# Sensors_Sch.net
KiCad netlist of a schematic drawn in Altium Designer
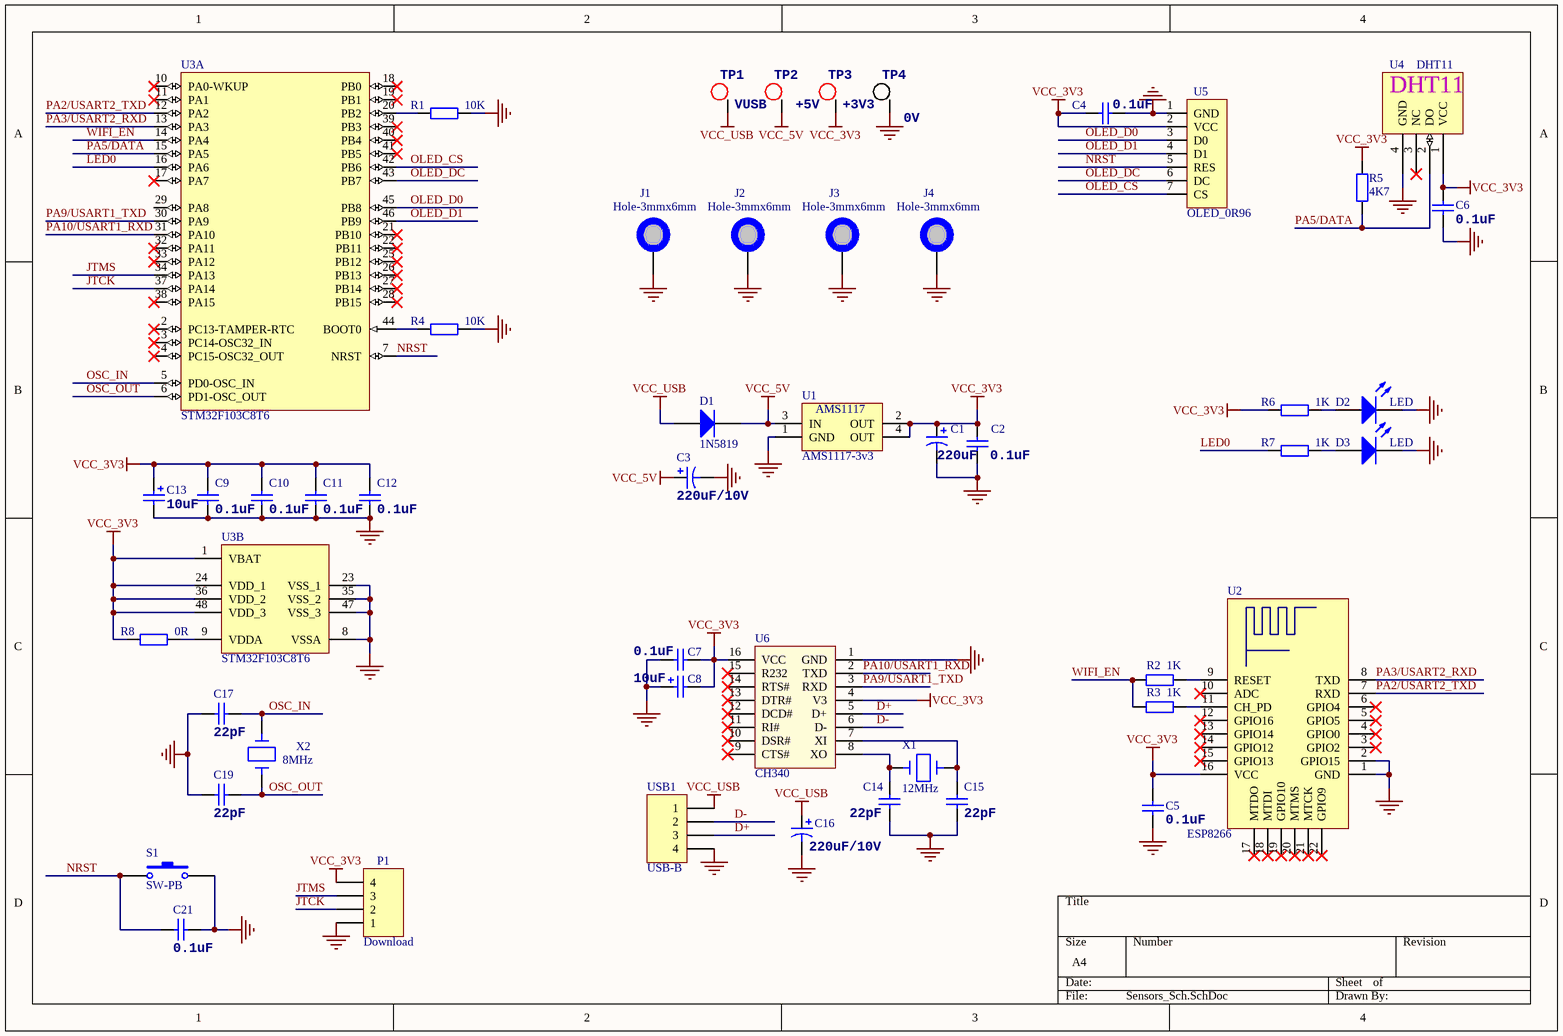
[diagram p0: Sensors_Sch.SchDoc]

(export (version "E")
  (design (tool "Eeschema 10.0.6"))
  (components
    (comp (ref "C1")
      (value "220uF")
      (footprint "C_SMD(6.3x5.3)")
      (description "CAP ALUM POLY 150UF 20% 10V SMD")
      (fields
        (field (name "MANUFACTURER") "KEMET")
        (field (name "MANUFACTURER PART NUMBER") "A765EB157M1ALAE022")
      )
      (libsource (lib "Desiger_Schlib") (part "Cap3"))
    )
    (comp (ref "C2")
      (value "0.1uF")
      (footprint "C0603")
      (description "CAP CER 10000PF 100V X7R 0603")
      (fields
        (field (name "MANUFACTURER") "TDK Corporation")
        (field (name "MANUFACTURER PART NUMBER") "C1608X7R2A103K080AA")
      )
      (libsource (lib "Desiger_Schlib") (part "Cap1"))
    )
    (comp (ref "C3")
      (value "220uF/10V")
      (footprint "C_SMD(6.3x5.3)")
      (description "CAP ALUM POLY 150UF 20% 10V SMD")
      (fields
        (field (name "MANUFACTURER") "KEMET")
        (field (name "MANUFACTURER PART NUMBER") "A765EB157M1ALAE022")
      )
      (libsource (lib "Desiger_Schlib") (part "Cap3"))
    )
    (comp (ref "C4")
      (value "0.1uF")
      (footprint "C0603")
      (description "CAP CER 10000PF 100V X7R 0603")
      (fields
        (field (name "MANUFACTURER") "TDK Corporation")
        (field (name "MANUFACTURER PART NUMBER") "C1608X7R2A103K080AA")
      )
      (libsource (lib "Desiger_Schlib") (part "Cap1"))
    )
    (comp (ref "C5")
      (value "0.1uF")
      (footprint "C0603")
      (description "CAP CER 10000PF 100V X7R 0603")
      (fields
        (field (name "MANUFACTURER") "TDK Corporation")
        (field (name "MANUFACTURER PART NUMBER") "C1608X7R2A103K080AA")
      )
      (libsource (lib "Desiger_Schlib") (part "Cap1"))
    )
    (comp (ref "C6")
      (value "0.1uF")
      (footprint "C0603")
      (description "CAP CER 10000PF 100V X7R 0603")
      (fields
        (field (name "MANUFACTURER") "TDK Corporation")
        (field (name "MANUFACTURER PART NUMBER") "C1608X7R2A103K080AA")
      )
      (libsource (lib "Desiger_Schlib") (part "Cap1"))
    )
    (comp (ref "C7")
      (value "0.1uF")
      (footprint "C0603")
      (description "CAP CER 10000PF 100V X7R 0603")
      (fields
        (field (name "MANUFACTURER") "TDK Corporation")
        (field (name "MANUFACTURER PART NUMBER") "C1608X7R2A103K080AA")
      )
      (libsource (lib "Desiger_Schlib") (part "Cap1"))
    )
    (comp (ref "C8")
      (value "10uF")
      (footprint "TAC1206")
      (description "CAP TANT 10UF 10V 10% 1206")
      (fields
        (field (name "MANUFACTURER") "KEMET")
        (field (name "MANUFACTURER PART NUMBER") "T491A106K010AT7280")
      )
      (libsource (lib "Desiger_Schlib") (part "Cap2"))
    )
    (comp (ref "C9")
      (value "0.1uF")
      (footprint "C0603")
      (description "CAP CER 10000PF 100V X7R 0603")
      (fields
        (field (name "MANUFACTURER") "TDK Corporation")
        (field (name "MANUFACTURER PART NUMBER") "C1608X7R2A103K080AA")
      )
      (libsource (lib "Desiger_Schlib") (part "Cap1"))
    )
    (comp (ref "C10")
      (value "0.1uF")
      (footprint "C0603")
      (description "CAP CER 10000PF 100V X7R 0603")
      (fields
        (field (name "MANUFACTURER") "TDK Corporation")
        (field (name "MANUFACTURER PART NUMBER") "C1608X7R2A103K080AA")
      )
      (libsource (lib "Desiger_Schlib") (part "Cap1"))
    )
    (comp (ref "C11")
      (value "0.1uF")
      (footprint "C0603")
      (description "CAP CER 10000PF 100V X7R 0603")
      (fields
        (field (name "MANUFACTURER") "TDK Corporation")
        (field (name "MANUFACTURER PART NUMBER") "C1608X7R2A103K080AA")
      )
      (libsource (lib "Desiger_Schlib") (part "Cap1"))
    )
    (comp (ref "C12")
      (value "0.1uF")
      (footprint "C0603")
      (description "CAP CER 10000PF 100V X7R 0603")
      (fields
        (field (name "MANUFACTURER") "TDK Corporation")
        (field (name "MANUFACTURER PART NUMBER") "C1608X7R2A103K080AA")
      )
      (libsource (lib "Desiger_Schlib") (part "Cap1"))
    )
    (comp (ref "C13")
      (value "10uF")
      (footprint "TAC1206")
      (description "CAP TANT 10UF 10V 10% 1206")
      (fields
        (field (name "MANUFACTURER") "KEMET")
        (field (name "MANUFACTURER PART NUMBER") "T491A106K010AT7280")
      )
      (libsource (lib "Desiger_Schlib") (part "Cap2"))
    )
    (comp (ref "C14")
      (value "22pF")
      (footprint "C0603")
      (description "CAP CER 10000PF 100V X7R 0603")
      (fields
        (field (name "MANUFACTURER") "TDK Corporation")
        (field (name "MANUFACTURER PART NUMBER") "C1608X7R2A103K080AA")
      )
      (libsource (lib "Desiger_Schlib") (part "Cap1"))
    )
    (comp (ref "C15")
      (value "22pF")
      (footprint "C0603")
      (description "CAP CER 10000PF 100V X7R 0603")
      (fields
        (field (name "MANUFACTURER") "TDK Corporation")
        (field (name "MANUFACTURER PART NUMBER") "C1608X7R2A103K080AA")
      )
      (libsource (lib "Desiger_Schlib") (part "Cap1"))
    )
    (comp (ref "C16")
      (value "220uF/10V")
      (footprint "C_SMD(6.3x5.3)")
      (description "CAP ALUM POLY 150UF 20% 10V SMD")
      (fields
        (field (name "MANUFACTURER") "KEMET")
        (field (name "MANUFACTURER PART NUMBER") "A765EB157M1ALAE022")
      )
      (libsource (lib "Desiger_Schlib") (part "Cap3"))
    )
    (comp (ref "C17")
      (value "22pF")
      (footprint "C0603")
      (description "CAP CER 10000PF 100V X7R 0603")
      (fields
        (field (name "MANUFACTURER") "TDK Corporation")
        (field (name "MANUFACTURER PART NUMBER") "C1608X7R2A103K080AA")
      )
      (libsource (lib "Desiger_Schlib") (part "Cap1"))
    )
    (comp (ref "C19")
      (value "22pF")
      (footprint "C0603")
      (description "CAP CER 10000PF 100V X7R 0603")
      (fields
        (field (name "MANUFACTURER") "TDK Corporation")
        (field (name "MANUFACTURER PART NUMBER") "C1608X7R2A103K080AA")
      )
      (libsource (lib "Desiger_Schlib") (part "Cap1"))
    )
    (comp (ref "C21")
      (value "0.1uF")
      (footprint "C0603")
      (description "CAP CER 10000PF 100V X7R 0603")
      (fields
        (field (name "MANUFACTURER") "TDK Corporation")
        (field (name "MANUFACTURER PART NUMBER") "C1608X7R2A103K080AA")
      )
      (libsource (lib "Desiger_Schlib") (part "Cap1"))
    )
    (comp (ref "D1")
      (value "1N5819")
      (footprint "Desiger_Pcblib:SOD123")
      (description "Default Diode")
      (fields (field (name "PUBLISHER") "Altium Limited"))
      (libsource (lib "Desiger_Schlib") (part "Diode"))
    )
    (comp (ref "D2")
      (value "LED")
      (footprint "LED_0603")
      (description "Typical RED GaAs LED")
      (fields (field (name "PUBLISHER") "Altium Limited"))
      (libsource (lib "Desiger_Schlib") (part "LED"))
    )
    (comp (ref "D3")
      (value "LED")
      (footprint "LED_0603")
      (description "Typical RED GaAs LED")
      (fields (field (name "PUBLISHER") "Altium Limited"))
      (libsource (lib "Desiger_Schlib") (part "LED"))
    )
    (comp (ref "J1")
      (value "Hole-3mmx6mm")
      (footprint "M3x7+6_L")
      (libsource (lib "Desiger_Schlib") (part "HOLED"))
    )
    (comp (ref "J2")
      (value "Hole-3mmx6mm")
      (footprint "M3x7+6_L")
      (libsource (lib "Desiger_Schlib") (part "HOLED"))
    )
    (comp (ref "J3")
      (value "Hole-3mmx6mm")
      (footprint "M3x7+6_L")
      (libsource (lib "Desiger_Schlib") (part "HOLED"))
    )
    (comp (ref "J4")
      (value "Hole-3mmx6mm")
      (footprint "M3x7+6_L")
      (libsource (lib "Desiger_Schlib") (part "HOLED"))
    )
    (comp (ref "P1")
      (value "Download")
      (footprint "HDR1X4")
      (description "Header, 4-Pin")
      (fields (field (name "PUBLISHER") "Altium Limited"))
      (libsource (lib "Miscellaneous Connectors") (part "Header 4"))
    )
    (comp (ref "R1")
      (value "10K")
      (footprint "R0603")
      (description "贴片电阻")
      (fields (field (name "版权归属") "源创客"))
      (libsource (lib "3.1   - 电阻-电容-电感") (part "R"))
    )
    (comp (ref "R2")
      (value "1K")
      (footprint "R0603")
      (description "贴片电阻")
      (fields (field (name "版权归属") "源创客"))
      (libsource (lib "3.1   - 电阻-电容-电感") (part "R"))
    )
    (comp (ref "R3")
      (value "1K")
      (footprint "R0603")
      (description "贴片电阻")
      (fields (field (name "版权归属") "源创客"))
      (libsource (lib "3.1   - 电阻-电容-电感") (part "R"))
    )
    (comp (ref "R4")
      (value "10K")
      (footprint "R0603")
      (description "贴片电阻")
      (fields (field (name "版权归属") "源创客"))
      (libsource (lib "3.1   - 电阻-电容-电感") (part "R"))
    )
    (comp (ref "R5")
      (value "4K7")
      (footprint "R0603")
      (description "贴片电阻")
      (fields (field (name "版权归属") "源创客"))
      (libsource (lib "3.1   - 电阻-电容-电感") (part "R"))
    )
    (comp (ref "R6")
      (value "1K")
      (footprint "R0603")
      (description "贴片电阻")
      (fields (field (name "版权归属") "源创客"))
      (libsource (lib "3.1   - 电阻-电容-电感") (part "R"))
    )
    (comp (ref "R7")
      (value "1K")
      (footprint "R0603")
      (description "贴片电阻")
      (fields (field (name "版权归属") "源创客"))
      (libsource (lib "3.1   - 电阻-电容-电感") (part "R"))
    )
    (comp (ref "R8")
      (value "0R")
      (footprint "R0603")
      (description "贴片电阻")
      (fields (field (name "版权归属") "源创客"))
      (libsource (lib "3.1   - 电阻-电容-电感") (part "R"))
    )
    (comp (ref "S1")
      (value "SW-PB")
      (footprint "micro button_2_SMD")
      (description "Switch")
      (fields (field (name "PUBLISHER") "Altium Limited"))
      (libsource (lib "Miscellaneous Devices") (part "SW-PB"))
    )
    (comp (ref "TP1")
      (value "VUSB")
      (footprint "TP")
      (description "正测试环")
      (libsource (lib "Desiger_Schlib") (part "TP+"))
    )
    (comp (ref "TP2")
      (value "+5V")
      (footprint "TP")
      (description "正测试环")
      (libsource (lib "Desiger_Schlib") (part "TP+"))
    )
    (comp (ref "TP3")
      (value "+3V3")
      (footprint "TP")
      (description "正测试环")
      (libsource (lib "Desiger_Schlib") (part "TP+"))
    )
    (comp (ref "TP4")
      (value "0V")
      (footprint "TP")
      (description "负测试环")
      (libsource (lib "Desiger_Schlib") (part "TP-"))
    )
    (comp (ref "U1")
      (value "AMS1117-3v3")
      (footprint "SOT223_L")
      (libsource (lib "Desiger_Schlib") (part "AMS1117-3v3"))
    )
    (comp (ref "U2")
      (value "ESP8266")
      (footprint "ESP8266")
      (libsource (lib "Desiger_Schlib") (part "ESP8266 Module"))
    )
    (comp (ref "U3")
      (value "STM32F103C8T6")
      (footprint "LQFP48 7X7_N")
      (libsource (lib "STMicroelectronics STM32 F1") (part "STM32F103C8T6"))
    )
    (comp (ref "U4")
      (value "DHT11")
      (footprint "DHT11")
      (description "GROVE TEMP/HUMIDITY SENSOR")
      (fields
        (field (name "MANUFACTURER") "Seeed Technology Co., Ltd")
        (field (name "MANUFACTURER PART NUMBER") "101020011")
      )
      (libsource (lib "Desiger_Schlib") (part "DHT11"))
    )
    (comp (ref "U5")
      (value "OLED_0R96")
      (footprint "OLED_0.96_SPI")
      (libsource (lib "Desiger_Schlib") (part "OLED_7P_0R96"))
    )
    (comp (ref "U6") (value "CH340") (footprint "SOIC_16") (libsource (lib "First Version") (part "CH340")))
    (comp (ref "USB1")
      (value "USB-B")
      (footprint "USB-B")
      (description "Header, 4-Pin")
      (fields (field (name "PUBLISHER") "Altium Limited"))
      (libsource (lib "") (part "Header 4_1"))
    )
    (comp (ref "X1")
      (value "12MHz")
      (footprint "HC-49SMD")
      (description "CRYSTAL 12.0000MHZ 18PF SMD")
      (fields
        (field (name "MANUFACTURER") "Abracon LLC")
        (field (name "MANUFACTURER PART NUMBER") "ABLS-12.000MHZ-B2-T")
      )
      (libsource (lib "Desiger_Schlib") (part "Crystal"))
    )
    (comp (ref "X2")
      (value "8MHz")
      (footprint "HC-49SMD")
      (description "CRYSTAL 12.0000MHZ 18PF SMD")
      (fields
        (field (name "MANUFACTURER") "Abracon LLC")
        (field (name "MANUFACTURER PART NUMBER") "ABLS-12.000MHZ-B2-T")
      )
      (libsource (lib "Desiger_Schlib") (part "Crystal"))
    )
  )
  (nets
    (net (code "1") (name "/D+") (class "Default")
      (node (ref "U6") (pin "5") (pinfunction "D+_5") (pintype "passive"))
      (node (ref "USB1") (pin "3") (pinfunction "3_3") (pintype "passive"))
    )
    (net (code "2") (name "/D-") (class "Default")
      (node (ref "U6") (pin "6") (pinfunction "D-_6") (pintype "passive"))
      (node (ref "USB1") (pin "2") (pinfunction "2_2") (pintype "passive"))
    )
    (net (code "3") (name "/JTCK") (class "Default")
      (node (ref "P1") (pin "2") (pinfunction "2_2") (pintype "passive"))
      (node (ref "U3") (pin "37") (pinfunction "PA14_37") (pintype "bidirectional"))
    )
    (net (code "4") (name "/JTMS") (class "Default")
      (node (ref "P1") (pin "3") (pinfunction "3_3") (pintype "passive"))
      (node (ref "U3") (pin "34") (pinfunction "PA13_34") (pintype "bidirectional"))
    )
    (net (code "5") (name "/LED0") (class "Default")
      (node (ref "R7") (pin "1") (pinfunction "1_1") (pintype "passive"))
      (node (ref "U3") (pin "16") (pinfunction "PA6_16") (pintype "bidirectional"))
    )
    (net (code "6") (name "/NRST") (class "Default")
      (node (ref "C21") (pin "2") (pinfunction "2_2") (pintype "passive"))
      (node (ref "S1") (pin "1") (pinfunction "1_1") (pintype "passive"))
      (node (ref "U3") (pin "7") (pinfunction "NRST_7") (pintype "bidirectional"))
      (node (ref "U5") (pin "5") (pinfunction "RES_5") (pintype "passive"))
    )
    (net (code "7") (name "/OLED_CS") (class "Default")
      (node (ref "U3") (pin "42") (pinfunction "PB6_42") (pintype "bidirectional"))
      (node (ref "U5") (pin "7") (pinfunction "CS_7") (pintype "passive"))
    )
    (net (code "8") (name "/OLED_D0") (class "Default")
      (node (ref "U3") (pin "45") (pinfunction "PB8_45") (pintype "bidirectional"))
      (node (ref "U5") (pin "3") (pinfunction "D0_3") (pintype "passive"))
    )
    (net (code "9") (name "/OLED_D1") (class "Default")
      (node (ref "U3") (pin "46") (pinfunction "PB9_46") (pintype "bidirectional"))
      (node (ref "U5") (pin "4") (pinfunction "D1_4") (pintype "passive"))
    )
    (net (code "10") (name "/OLED_DC") (class "Default")
      (node (ref "U3") (pin "43") (pinfunction "PB7_43") (pintype "bidirectional"))
      (node (ref "U5") (pin "6") (pinfunction "DC_6") (pintype "passive"))
    )
    (net (code "11") (name "/OSC_IN") (class "Default")
      (node (ref "C17") (pin "1") (pinfunction "1_1") (pintype "passive"))
      (node (ref "U3") (pin "5") (pinfunction "PD0-OSC_IN_5") (pintype "bidirectional"))
      (node (ref "X2") (pin "2") (pinfunction "X2_2") (pintype "passive"))
    )
    (net (code "12") (name "/OSC_OUT") (class "Default")
      (node (ref "C19") (pin "1") (pinfunction "1_1") (pintype "passive"))
      (node (ref "U3") (pin "6") (pinfunction "PD1-OSC_OUT_6") (pintype "bidirectional"))
      (node (ref "X2") (pin "1") (pinfunction "X1_1") (pintype "passive"))
    )
    (net (code "13") (name "/PA2{slash}USART2_TXD") (class "Default")
      (node (ref "U2") (pin "7") (pinfunction "RXD_7") (pintype "passive"))
      (node (ref "U3") (pin "12") (pinfunction "PA2_12") (pintype "bidirectional"))
    )
    (net (code "14") (name "/PA3{slash}USART2_RXD") (class "Default")
      (node (ref "U2") (pin "8") (pinfunction "TXD_8") (pintype "passive"))
      (node (ref "U3") (pin "13") (pinfunction "PA3_13") (pintype "bidirectional"))
    )
    (net (code "15") (name "/PA5{slash}DATA") (class "Default")
      (node (ref "R5") (pin "1") (pinfunction "1_1") (pintype "passive"))
      (node (ref "U3") (pin "15") (pinfunction "PA5_15") (pintype "bidirectional"))
      (node (ref "U4") (pin "2") (pinfunction "DO_2") (pintype "bidirectional"))
    )
    (net (code "16") (name "/PA9{slash}USART1_TXD") (class "Default")
      (node (ref "U3") (pin "30") (pinfunction "PA9_30") (pintype "bidirectional"))
      (node (ref "U6") (pin "3") (pinfunction "RXD_3") (pintype "passive"))
    )
    (net (code "17") (name "/PA10{slash}USART1_RXD") (class "Default")
      (node (ref "U3") (pin "31") (pinfunction "PA10_31") (pintype "bidirectional"))
      (node (ref "U6") (pin "2") (pinfunction "TXD_2") (pintype "passive"))
    )
    (net (code "18") (name "/WIFI_EN") (class "Default")
      (node (ref "R2") (pin "1") (pinfunction "1_1") (pintype "passive"))
      (node (ref "R3") (pin "1") (pinfunction "1_1") (pintype "passive"))
      (node (ref "U3") (pin "14") (pinfunction "PA4_14") (pintype "bidirectional"))
    )
    (net (code "19") (name "GND") (class "Default")
      (node (ref "C1") (pin "2") (pinfunction "-_2") (pintype "passive"))
      (node (ref "C10") (pin "1") (pinfunction "1_1") (pintype "passive"))
      (node (ref "C11") (pin "1") (pinfunction "1_1") (pintype "passive"))
      (node (ref "C12") (pin "1") (pinfunction "1_1") (pintype "passive"))
      (node (ref "C13") (pin "2") (pinfunction "-_2") (pintype "passive"))
      (node (ref "C14") (pin "1") (pinfunction "1_1") (pintype "passive"))
      (node (ref "C15") (pin "1") (pinfunction "1_1") (pintype "passive"))
      (node (ref "C16") (pin "2") (pinfunction "-_2") (pintype "passive"))
      (node (ref "C17") (pin "2") (pinfunction "2_2") (pintype "passive"))
      (node (ref "C19") (pin "2") (pinfunction "2_2") (pintype "passive"))
      (node (ref "C2") (pin "1") (pinfunction "1_1") (pintype "passive"))
      (node (ref "C21") (pin "1") (pinfunction "1_1") (pintype "passive"))
      (node (ref "C3") (pin "2") (pinfunction "-_2") (pintype "passive"))
      (node (ref "C4") (pin "1") (pinfunction "1_1") (pintype "passive"))
      (node (ref "C5") (pin "2") (pinfunction "2_2") (pintype "passive"))
      (node (ref "C6") (pin "2") (pinfunction "2_2") (pintype "passive"))
      (node (ref "C7") (pin "2") (pinfunction "2_2") (pintype "passive"))
      (node (ref "C8") (pin "1") (pinfunction "+_1") (pintype "passive"))
      (node (ref "C9") (pin "1") (pinfunction "1_1") (pintype "passive"))
      (node (ref "D2") (pin "2") (pinfunction "K_2") (pintype "passive"))
      (node (ref "D3") (pin "2") (pinfunction "K_2") (pintype "passive"))
      (node (ref "J1") (pin "0") (pinfunction "0_0") (pintype "passive"))
      (node (ref "J2") (pin "0") (pinfunction "0_0") (pintype "passive"))
      (node (ref "J3") (pin "0") (pinfunction "0_0") (pintype "passive"))
      (node (ref "J4") (pin "0") (pinfunction "0_0") (pintype "passive"))
      (node (ref "P1") (pin "1") (pinfunction "1_1") (pintype "passive"))
      (node (ref "R1") (pin "2") (pinfunction "2_2") (pintype "passive"))
      (node (ref "R4") (pin "2") (pinfunction "2_2") (pintype "passive"))
      (node (ref "S1") (pin "2") (pinfunction "2_2") (pintype "passive"))
      (node (ref "TP4") (pin "1") (pinfunction "1_1") (pintype "passive"))
      (node (ref "U1") (pin "1") (pinfunction "GND_1") (pintype "passive"))
      (node (ref "U2") (pin "1") (pinfunction "GND_1") (pintype "passive"))
      (node (ref "U2") (pin "2") (pinfunction "GPIO15_2") (pintype "passive"))
      (node (ref "U3") (pin "23") (pinfunction "VSS_1_23") (pintype "passive"))
      (node (ref "U3") (pin "35") (pinfunction "VSS_2_35") (pintype "passive"))
      (node (ref "U3") (pin "47") (pinfunction "VSS_3_47") (pintype "passive"))
      (node (ref "U3") (pin "8") (pinfunction "VSSA_8") (pintype "passive"))
      (node (ref "U4") (pin "4") (pinfunction "GND_4") (pintype "passive"))
      (node (ref "U5") (pin "1") (pinfunction "GND_1") (pintype "passive"))
      (node (ref "U6") (pin "1") (pinfunction "GND_1") (pintype "passive"))
      (node (ref "USB1") (pin "4") (pinfunction "4_4") (pintype "passive"))
    )
    (net (code "20") (name "Net-(D2-A)") (class "Default")
      (node (ref "D2") (pin "1") (pinfunction "A_1") (pintype "passive"))
      (node (ref "R6") (pin "2") (pinfunction "2_2") (pintype "passive"))
    )
    (net (code "21") (name "Net-(D3-A)") (class "Default")
      (node (ref "D3") (pin "1") (pinfunction "A_1") (pintype "passive"))
      (node (ref "R7") (pin "2") (pinfunction "2_2") (pintype "passive"))
    )
    (net (code "22") (name "Net-(U2-CH_PD)") (class "Default")
      (node (ref "R3") (pin "2") (pinfunction "2_2") (pintype "passive"))
      (node (ref "U2") (pin "11") (pinfunction "CH_PD_11") (pintype "passive"))
    )
    (net (code "23") (name "Net-(U2-RESET)") (class "Default")
      (node (ref "R2") (pin "2") (pinfunction "2_2") (pintype "passive"))
      (node (ref "U2") (pin "9") (pinfunction "RESET_9") (pintype "passive"))
    )
    (net (code "24") (name "Net-(U3A-BOOT0)") (class "Default")
      (node (ref "R4") (pin "1") (pinfunction "1_1") (pintype "passive"))
      (node (ref "U3") (pin "44") (pinfunction "BOOT0_44") (pintype "input"))
    )
    (net (code "25") (name "Net-(U3A-PB2)") (class "Default")
      (node (ref "R1") (pin "1") (pinfunction "1_1") (pintype "passive"))
      (node (ref "U3") (pin "20") (pinfunction "PB2_20") (pintype "bidirectional"))
    )
    (net (code "26") (name "Net-(U3B-VDDA)") (class "Default")
      (node (ref "R8") (pin "2") (pinfunction "2_2") (pintype "passive"))
      (node (ref "U3") (pin "9") (pinfunction "VDDA_9") (pintype "passive"))
    )
    (net (code "27") (name "Net-(U6-XI)") (class "Default")
      (node (ref "C15") (pin "2") (pinfunction "2_2") (pintype "passive"))
      (node (ref "U6") (pin "7") (pinfunction "XI_7") (pintype "passive"))
      (node (ref "X1") (pin "1") (pinfunction "X1_1") (pintype "passive"))
    )
    (net (code "28") (name "Net-(U6-XO)") (class "Default")
      (node (ref "C14") (pin "2") (pinfunction "2_2") (pintype "passive"))
      (node (ref "U6") (pin "8") (pinfunction "XO_8") (pintype "passive"))
      (node (ref "X1") (pin "2") (pinfunction "X2_2") (pintype "passive"))
    )
    (net (code "29") (name "VCC_3V3") (class "Default")
      (node (ref "C1") (pin "1") (pinfunction "+_1") (pintype "passive"))
      (node (ref "C10") (pin "2") (pinfunction "2_2") (pintype "passive"))
      (node (ref "C11") (pin "2") (pinfunction "2_2") (pintype "passive"))
      (node (ref "C12") (pin "2") (pinfunction "2_2") (pintype "passive"))
      (node (ref "C13") (pin "1") (pinfunction "+_1") (pintype "passive"))
      (node (ref "C2") (pin "2") (pinfunction "2_2") (pintype "passive"))
      (node (ref "C4") (pin "2") (pinfunction "2_2") (pintype "passive"))
      (node (ref "C5") (pin "1") (pinfunction "1_1") (pintype "passive"))
      (node (ref "C6") (pin "1") (pinfunction "1_1") (pintype "passive"))
      (node (ref "C7") (pin "1") (pinfunction "1_1") (pintype "passive"))
      (node (ref "C8") (pin "2") (pinfunction "-_2") (pintype "passive"))
      (node (ref "C9") (pin "2") (pinfunction "2_2") (pintype "passive"))
      (node (ref "P1") (pin "4") (pinfunction "4_4") (pintype "passive"))
      (node (ref "R5") (pin "2") (pinfunction "2_2") (pintype "passive"))
      (node (ref "R6") (pin "1") (pinfunction "1_1") (pintype "passive"))
      (node (ref "R8") (pin "1") (pinfunction "1_1") (pintype "passive"))
      (node (ref "TP3") (pin "1") (pinfunction "1_1") (pintype "passive"))
      (node (ref "U1") (pin "2") (pinfunction "OUT_2") (pintype "passive"))
      (node (ref "U1") (pin "4") (pinfunction "OUT_4") (pintype "passive"))
      (node (ref "U2") (pin "16") (pinfunction "VCC_16") (pintype "passive"))
      (node (ref "U3") (pin "1") (pinfunction "VBAT_1") (pintype "passive"))
      (node (ref "U3") (pin "24") (pinfunction "VDD_1_24") (pintype "passive"))
      (node (ref "U3") (pin "36") (pinfunction "VDD_2_36") (pintype "passive"))
      (node (ref "U3") (pin "48") (pinfunction "VDD_3_48") (pintype "passive"))
      (node (ref "U4") (pin "1") (pinfunction "VCC_1") (pintype "passive"))
      (node (ref "U5") (pin "2") (pinfunction "VCC_2") (pintype "passive"))
      (node (ref "U6") (pin "16") (pinfunction "VCC_16") (pintype "passive"))
      (node (ref "U6") (pin "4") (pinfunction "V3_4") (pintype "passive"))
    )
    (net (code "30") (name "VCC_5V") (class "Default")
      (node (ref "C3") (pin "1") (pinfunction "+_1") (pintype "passive"))
      (node (ref "D1") (pin "2") (pinfunction "K_2") (pintype "passive"))
      (node (ref "TP2") (pin "1") (pinfunction "1_1") (pintype "passive"))
      (node (ref "U1") (pin "3") (pinfunction "IN_3") (pintype "passive"))
    )
    (net (code "31") (name "VCC_USB") (class "Default")
      (node (ref "C16") (pin "1") (pinfunction "+_1") (pintype "passive"))
      (node (ref "D1") (pin "1") (pinfunction "A_1") (pintype "passive"))
      (node (ref "TP1") (pin "1") (pinfunction "1_1") (pintype "passive"))
      (node (ref "USB1") (pin "1") (pinfunction "1_1") (pintype "passive"))
    )
    (net (code "32") (name "unconnected-(U2-ADC-Pad10)") (class "Default")
      (node (ref "U2") (pin "10") (pinfunction "ADC_10") (pintype "passive+no_connect"))
    )
    (net (code "33") (name "unconnected-(U2-GPIO0-Pad4)") (class "Default")
      (node (ref "U2") (pin "4") (pinfunction "GPIO0_4") (pintype "passive+no_connect"))
    )
    (net (code "34") (name "unconnected-(U2-GPIO2-Pad3)") (class "Default")
      (node (ref "U2") (pin "3") (pinfunction "GPIO2_3") (pintype "passive+no_connect"))
    )
    (net (code "35") (name "unconnected-(U2-GPIO4-Pad6)") (class "Default")
      (node (ref "U2") (pin "6") (pinfunction "GPIO4_6") (pintype "passive+no_connect"))
    )
    (net (code "36") (name "unconnected-(U2-GPIO5-Pad5)") (class "Default")
      (node (ref "U2") (pin "5") (pinfunction "GPIO5_5") (pintype "passive+no_connect"))
    )
    (net (code "37") (name "unconnected-(U2-GPIO9-Pad22)") (class "Default")
      (node (ref "U2") (pin "22") (pinfunction "GPIO9_22") (pintype "passive+no_connect"))
    )
    (net (code "38") (name "unconnected-(U2-GPIO10-Pad19)") (class "Default")
      (node (ref "U2") (pin "19") (pinfunction "GPIO10_19") (pintype "passive+no_connect"))
    )
    (net (code "39") (name "unconnected-(U2-GPIO12-Pad14)") (class "Default")
      (node (ref "U2") (pin "14") (pinfunction "GPIO12_14") (pintype "passive+no_connect"))
    )
    (net (code "40") (name "unconnected-(U2-GPIO13-Pad15)") (class "Default")
      (node (ref "U2") (pin "15") (pinfunction "GPIO13_15") (pintype "passive+no_connect"))
    )
    (net (code "41") (name "unconnected-(U2-GPIO14-Pad13)") (class "Default")
      (node (ref "U2") (pin "13") (pinfunction "GPIO14_13") (pintype "passive+no_connect"))
    )
    (net (code "42") (name "unconnected-(U2-GPIO16-Pad12)") (class "Default")
      (node (ref "U2") (pin "12") (pinfunction "GPIO16_12") (pintype "passive+no_connect"))
    )
    (net (code "43") (name "unconnected-(U2-MTCK-Pad21)") (class "Default")
      (node (ref "U2") (pin "21") (pinfunction "MTCK_21") (pintype "passive+no_connect"))
    )
    (net (code "44") (name "unconnected-(U2-MTDI-Pad18)") (class "Default")
      (node (ref "U2") (pin "18") (pinfunction "MTDI_18") (pintype "passive+no_connect"))
    )
    (net (code "45") (name "unconnected-(U2-MTDO-Pad17)") (class "Default")
      (node (ref "U2") (pin "17") (pinfunction "MTDO_17") (pintype "passive+no_connect"))
    )
    (net (code "46") (name "unconnected-(U2-MTMS-Pad20)") (class "Default")
      (node (ref "U2") (pin "20") (pinfunction "MTMS_20") (pintype "passive+no_connect"))
    )
    (net (code "47") (name "unconnected-(U3A-PA0-WKUP-Pad10)") (class "Default")
      (node (ref "U3") (pin "10") (pinfunction "PA0-WKUP_10") (pintype "bidirectional+no_connect"))
    )
    (net (code "48") (name "unconnected-(U3A-PA1-Pad11)") (class "Default")
      (node (ref "U3") (pin "11") (pinfunction "PA1_11") (pintype "bidirectional+no_connect"))
    )
    (net (code "49") (name "unconnected-(U3A-PA7-Pad17)") (class "Default")
      (node (ref "U3") (pin "17") (pinfunction "PA7_17") (pintype "bidirectional+no_connect"))
    )
    (net (code "50") (name "unconnected-(U3A-PA8-Pad29)") (class "Default")
      (node (ref "U3") (pin "29") (pinfunction "PA8_29") (pintype "bidirectional"))
    )
    (net (code "51") (name "unconnected-(U3A-PA11-Pad32)") (class "Default")
      (node (ref "U3") (pin "32") (pinfunction "PA11_32") (pintype "bidirectional+no_connect"))
    )
    (net (code "52") (name "unconnected-(U3A-PA12-Pad33)") (class "Default")
      (node (ref "U3") (pin "33") (pinfunction "PA12_33") (pintype "bidirectional+no_connect"))
    )
    (net (code "53") (name "unconnected-(U3A-PA15-Pad38)") (class "Default")
      (node (ref "U3") (pin "38") (pinfunction "PA15_38") (pintype "bidirectional+no_connect"))
    )
    (net (code "54") (name "unconnected-(U3A-PB0-Pad18)") (class "Default")
      (node (ref "U3") (pin "18") (pinfunction "PB0_18") (pintype "bidirectional+no_connect"))
    )
    (net (code "55") (name "unconnected-(U3A-PB1-Pad19)") (class "Default")
      (node (ref "U3") (pin "19") (pinfunction "PB1_19") (pintype "bidirectional+no_connect"))
    )
    (net (code "56") (name "unconnected-(U3A-PB3-Pad39)") (class "Default")
      (node (ref "U3") (pin "39") (pinfunction "PB3_39") (pintype "bidirectional+no_connect"))
    )
    (net (code "57") (name "unconnected-(U3A-PB4-Pad40)") (class "Default")
      (node (ref "U3") (pin "40") (pinfunction "PB4_40") (pintype "bidirectional+no_connect"))
    )
    (net (code "58") (name "unconnected-(U3A-PB5-Pad41)") (class "Default")
      (node (ref "U3") (pin "41") (pinfunction "PB5_41") (pintype "bidirectional+no_connect"))
    )
    (net (code "59") (name "unconnected-(U3A-PB10-Pad21)") (class "Default")
      (node (ref "U3") (pin "21") (pinfunction "PB10_21") (pintype "bidirectional+no_connect"))
    )
    (net (code "60") (name "unconnected-(U3A-PB11-Pad22)") (class "Default")
      (node (ref "U3") (pin "22") (pinfunction "PB11_22") (pintype "bidirectional+no_connect"))
    )
    (net (code "61") (name "unconnected-(U3A-PB12-Pad25)") (class "Default")
      (node (ref "U3") (pin "25") (pinfunction "PB12_25") (pintype "bidirectional+no_connect"))
    )
    (net (code "62") (name "unconnected-(U3A-PB13-Pad26)") (class "Default")
      (node (ref "U3") (pin "26") (pinfunction "PB13_26") (pintype "bidirectional+no_connect"))
    )
    (net (code "63") (name "unconnected-(U3A-PB14-Pad27)") (class "Default")
      (node (ref "U3") (pin "27") (pinfunction "PB14_27") (pintype "bidirectional+no_connect"))
    )
    (net (code "64") (name "unconnected-(U3A-PB15-Pad28)") (class "Default")
      (node (ref "U3") (pin "28") (pinfunction "PB15_28") (pintype "bidirectional+no_connect"))
    )
    (net (code "65") (name "unconnected-(U3A-PC13-TAMPER-RTC-Pad2)") (class "Default")
      (node (ref "U3") (pin "2") (pinfunction "PC13-TAMPER-RTC_2") (pintype "bidirectional+no_connect"))
    )
    (net (code "66") (name "unconnected-(U3A-PC14-OSC32_IN-Pad3)") (class "Default")
      (node (ref "U3") (pin "3") (pinfunction "PC14-OSC32_IN_3") (pintype "bidirectional+no_connect"))
    )
    (net (code "67") (name "unconnected-(U3A-PC15-OSC32_OUT-Pad4)") (class "Default")
      (node (ref "U3") (pin "4") (pinfunction "PC15-OSC32_OUT_4") (pintype "bidirectional+no_connect"))
    )
    (net (code "68") (name "unconnected-(U4-NC-Pad3)") (class "Default")
      (node (ref "U4") (pin "3") (pinfunction "NC_3") (pintype "passive+no_connect"))
    )
    (net (code "69") (name "unconnected-(U6-CTS#-Pad9)") (class "Default")
      (node (ref "U6") (pin "9") (pinfunction "CTS#_9") (pintype "passive+no_connect"))
    )
    (net (code "70") (name "unconnected-(U6-DCD#-Pad12)") (class "Default")
      (node (ref "U6") (pin "12") (pinfunction "DCD#_12") (pintype "passive+no_connect"))
    )
    (net (code "71") (name "unconnected-(U6-DSR#-Pad10)") (class "Default")
      (node (ref "U6") (pin "10") (pinfunction "DSR#_10") (pintype "passive+no_connect"))
    )
    (net (code "72") (name "unconnected-(U6-DTR#-Pad13)") (class "Default")
      (node (ref "U6") (pin "13") (pinfunction "DTR#_13") (pintype "passive+no_connect"))
    )
    (net (code "73") (name "unconnected-(U6-R232-Pad15)") (class "Default")
      (node (ref "U6") (pin "15") (pinfunction "R232_15") (pintype "passive+no_connect"))
    )
    (net (code "74") (name "unconnected-(U6-RI#-Pad11)") (class "Default")
      (node (ref "U6") (pin "11") (pinfunction "RI#_11") (pintype "passive+no_connect"))
    )
    (net (code "75") (name "unconnected-(U6-RTS#-Pad14)") (class "Default")
      (node (ref "U6") (pin "14") (pinfunction "RTS#_14") (pintype "passive+no_connect"))
    )
  )
)
